# Analog_Shield.net
KiCad netlist of a schematic drawn in EAGLE
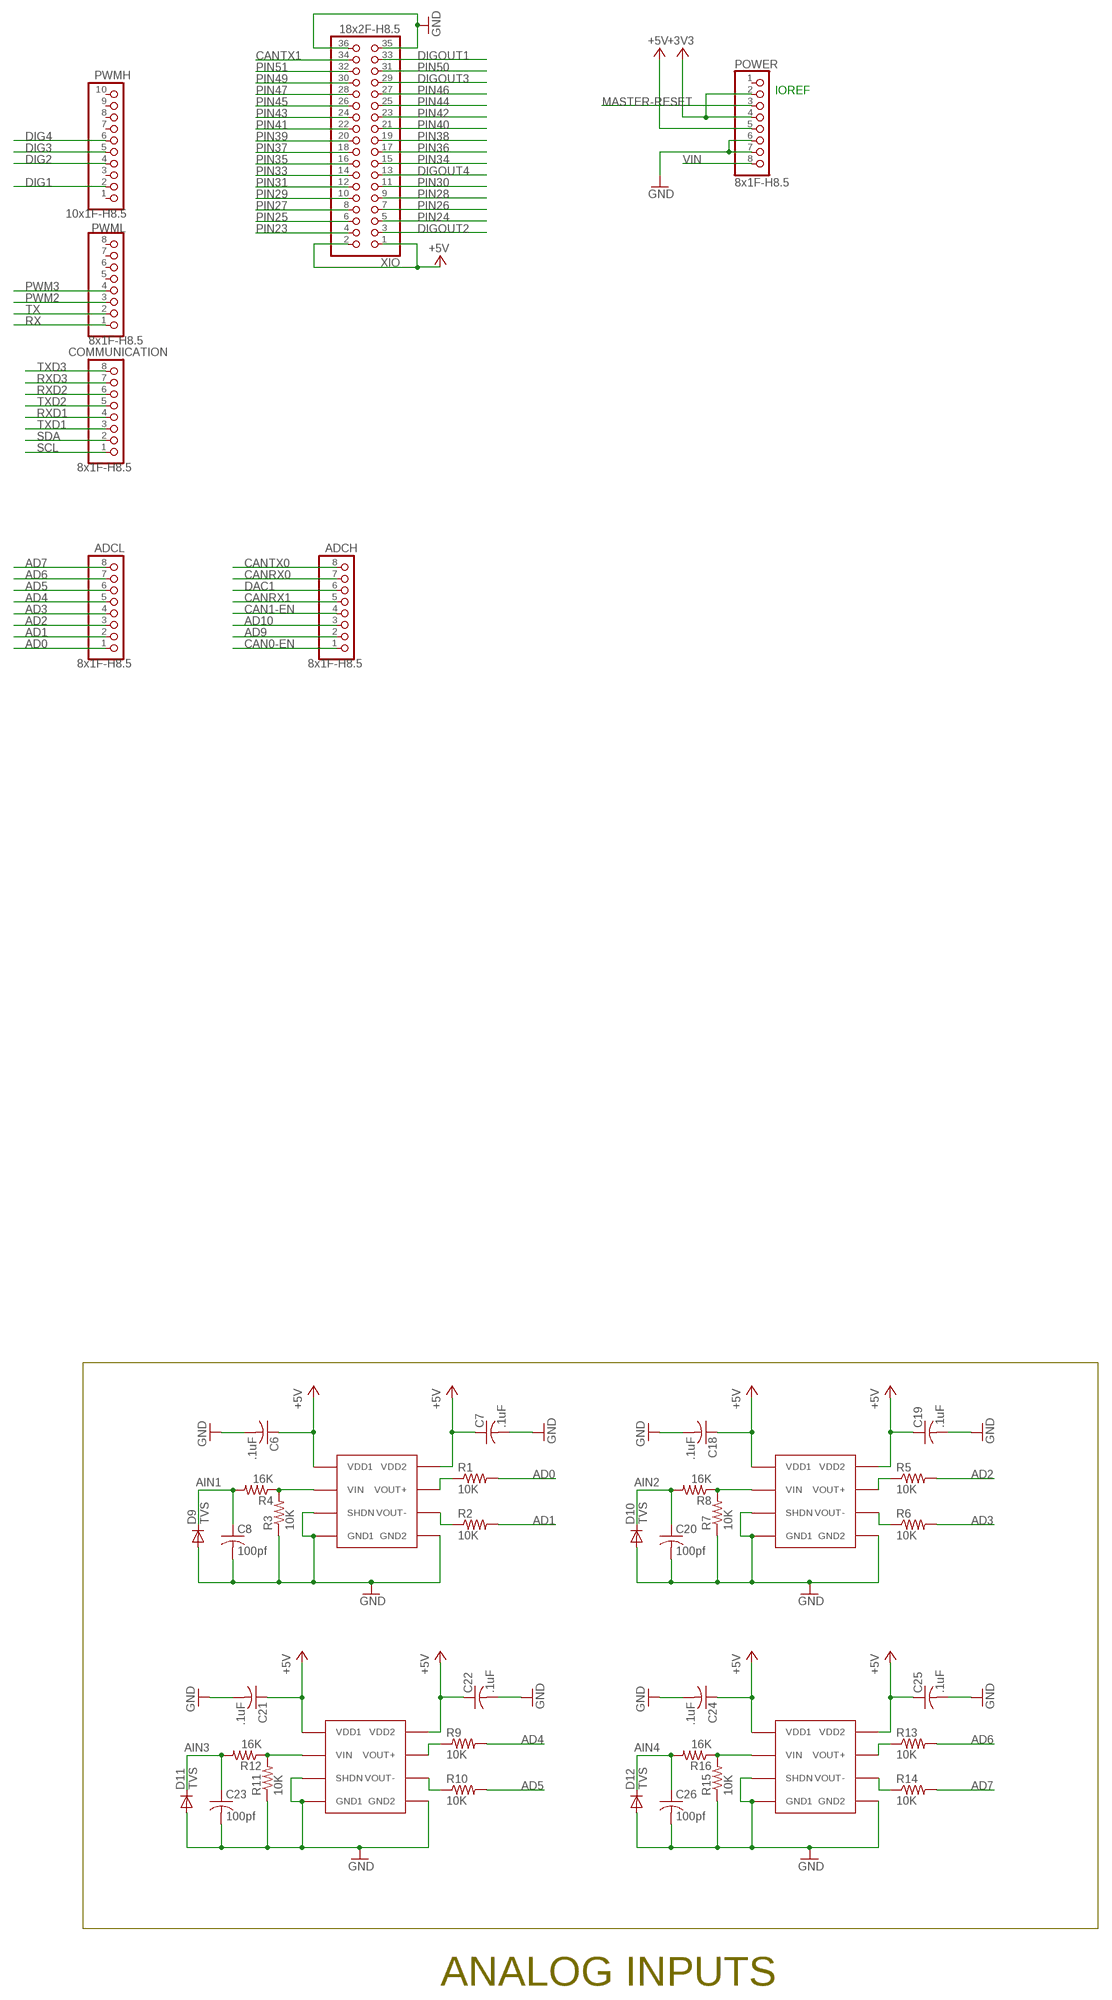
[diagram p0: schematic, sheet 1]

(export (version "E")
  (design (tool "Eeschema 10.0.6"))
  (components
    (comp (ref "ADCH")
      (value "8x1F-H8.5")
      (footprint "eagle-import:1X08")
      (libsource (lib "eagle-import") (part "PINHD-1X8"))
    )
    (comp (ref "ADCL")
      (value "8x1F-H8.5")
      (footprint "eagle-import:1X08")
      (libsource (lib "eagle-import") (part "PINHD-1X8"))
    )
    (comp (ref "C6")
      (value ".1uF")
      (footprint "eagle-import:C0603")
      (libsource (lib "eagle-import") (part "C-USC0603"))
    )
    (comp (ref "C7")
      (value ".1uF")
      (footprint "eagle-import:C0603")
      (libsource (lib "eagle-import") (part "C-USC0603"))
    )
    (comp (ref "C8")
      (value "100pf")
      (footprint "eagle-import:C0603")
      (libsource (lib "eagle-import") (part "C-USC0603"))
    )
    (comp (ref "C18")
      (value ".1uF")
      (footprint "eagle-import:C0603")
      (libsource (lib "eagle-import") (part "C-USC0603"))
    )
    (comp (ref "C19")
      (value ".1uF")
      (footprint "eagle-import:C0603")
      (libsource (lib "eagle-import") (part "C-USC0603"))
    )
    (comp (ref "C20")
      (value "100pf")
      (footprint "eagle-import:C0603")
      (libsource (lib "eagle-import") (part "C-USC0603"))
    )
    (comp (ref "C21")
      (value ".1uF")
      (footprint "eagle-import:C0603")
      (libsource (lib "eagle-import") (part "C-USC0603"))
    )
    (comp (ref "C22")
      (value ".1uF")
      (footprint "eagle-import:C0603")
      (libsource (lib "eagle-import") (part "C-USC0603"))
    )
    (comp (ref "C23")
      (value "100pf")
      (footprint "eagle-import:C0603")
      (libsource (lib "eagle-import") (part "C-USC0603"))
    )
    (comp (ref "C24")
      (value ".1uF")
      (footprint "eagle-import:C0603")
      (libsource (lib "eagle-import") (part "C-USC0603"))
    )
    (comp (ref "C25")
      (value ".1uF")
      (footprint "eagle-import:C0603")
      (libsource (lib "eagle-import") (part "C-USC0603"))
    )
    (comp (ref "C26")
      (value "100pf")
      (footprint "eagle-import:C0603")
      (libsource (lib "eagle-import") (part "C-USC0603"))
    )
    (comp (ref "COMMUNICATION")
      (value "8x1F-H8.5")
      (footprint "eagle-import:1X08")
      (libsource (lib "eagle-import") (part "PINHD-1X8"))
    )
    (comp (ref "D9")
      (value "TVS")
      (footprint "eagle-import:SOD-323")
      (libsource (lib "eagle-import") (part "DIODESOD"))
    )
    (comp (ref "D10")
      (value "TVS")
      (footprint "eagle-import:SOD-323")
      (libsource (lib "eagle-import") (part "DIODESOD"))
    )
    (comp (ref "D11")
      (value "TVS")
      (footprint "eagle-import:SOD-323")
      (libsource (lib "eagle-import") (part "DIODESOD"))
    )
    (comp (ref "D12")
      (value "TVS")
      (footprint "eagle-import:SOD-323")
      (libsource (lib "eagle-import") (part "DIODESOD"))
    )
    (comp (ref "POWER")
      (value "8x1F-H8.5")
      (footprint "eagle-import:1X08")
      (libsource (lib "eagle-import") (part "PINHD-1X8"))
    )
    (comp (ref "PWMH")
      (value "10x1F-H8.5")
      (footprint "eagle-import:1X10")
      (libsource (lib "eagle-import") (part "PINHD-1X10"))
    )
    (comp (ref "PWML")
      (value "8x1F-H8.5")
      (footprint "eagle-import:1X08")
      (libsource (lib "eagle-import") (part "PINHD-1X8"))
    )
    (comp (ref "R1")
      (value "10K")
      (footprint "eagle-import:R0603")
      (libsource (lib "eagle-import") (part "R-US_R0603"))
    )
    (comp (ref "R2")
      (value "10K")
      (footprint "eagle-import:R0603")
      (libsource (lib "eagle-import") (part "R-US_R0603"))
    )
    (comp (ref "R3")
      (value "10K")
      (footprint "eagle-import:R0603")
      (libsource (lib "eagle-import") (part "R-US_R0603"))
    )
    (comp (ref "R4")
      (value "16K")
      (footprint "eagle-import:R0603")
      (libsource (lib "eagle-import") (part "R-US_R0603"))
    )
    (comp (ref "R5")
      (value "10K")
      (footprint "eagle-import:R0603")
      (libsource (lib "eagle-import") (part "R-US_R0603"))
    )
    (comp (ref "R6")
      (value "10K")
      (footprint "eagle-import:R0603")
      (libsource (lib "eagle-import") (part "R-US_R0603"))
    )
    (comp (ref "R7")
      (value "10K")
      (footprint "eagle-import:R0603")
      (libsource (lib "eagle-import") (part "R-US_R0603"))
    )
    (comp (ref "R8")
      (value "16K")
      (footprint "eagle-import:R0603")
      (libsource (lib "eagle-import") (part "R-US_R0603"))
    )
    (comp (ref "R9")
      (value "10K")
      (footprint "eagle-import:R0603")
      (libsource (lib "eagle-import") (part "R-US_R0603"))
    )
    (comp (ref "R10")
      (value "10K")
      (footprint "eagle-import:R0603")
      (libsource (lib "eagle-import") (part "R-US_R0603"))
    )
    (comp (ref "R11")
      (value "10K")
      (footprint "eagle-import:R0603")
      (libsource (lib "eagle-import") (part "R-US_R0603"))
    )
    (comp (ref "R12")
      (value "16K")
      (footprint "eagle-import:R0603")
      (libsource (lib "eagle-import") (part "R-US_R0603"))
    )
    (comp (ref "R13")
      (value "10K")
      (footprint "eagle-import:R0603")
      (libsource (lib "eagle-import") (part "R-US_R0603"))
    )
    (comp (ref "R14")
      (value "10K")
      (footprint "eagle-import:R0603")
      (libsource (lib "eagle-import") (part "R-US_R0603"))
    )
    (comp (ref "R15")
      (value "10K")
      (footprint "eagle-import:R0603")
      (libsource (lib "eagle-import") (part "R-US_R0603"))
    )
    (comp (ref "R16")
      (value "16K")
      (footprint "eagle-import:R0603")
      (libsource (lib "eagle-import") (part "R-US_R0603"))
    )
    (comp (ref "U$1")
      (value "ACPL-C87A-000E")
      (footprint "eagle-import:SO8-WIDE")
      (libsource (lib "eagle-import") (part "ACPL-C87A-000E"))
    )
    (comp (ref "U$10")
      (value "ACPL-C87A-000E")
      (footprint "eagle-import:SO8-WIDE")
      (libsource (lib "eagle-import") (part "ACPL-C87A-000E"))
    )
    (comp (ref "U$11")
      (value "ACPL-C87A-000E")
      (footprint "eagle-import:SO8-WIDE")
      (libsource (lib "eagle-import") (part "ACPL-C87A-000E"))
    )
    (comp (ref "U$12")
      (value "ACPL-C87A-000E")
      (footprint "eagle-import:SO8-WIDE")
      (libsource (lib "eagle-import") (part "ACPL-C87A-000E"))
    )
    (comp (ref "XIO")
      (value "18x2F-H8.5")
      (footprint "eagle-import:2X18")
      (libsource (lib "eagle-import") (part "PINHD-2X18"))
    )
  )
  (nets
    (net (code "1") (name "+3V3") (class "Default")
      (node (ref "POWER") (pin "2") (pinfunction "2_2") (pintype "passive"))
      (node (ref "POWER") (pin "4") (pinfunction "4_4") (pintype "passive"))
    )
    (net (code "2") (name "+5V") (class "Default")
      (node (ref "C18") (pin "1") (pinfunction "1_1") (pintype "passive"))
      (node (ref "C19") (pin "1") (pinfunction "1_1") (pintype "passive"))
      (node (ref "C21") (pin "1") (pinfunction "1_1") (pintype "passive"))
      (node (ref "C22") (pin "1") (pinfunction "1_1") (pintype "passive"))
      (node (ref "C24") (pin "1") (pinfunction "1_1") (pintype "passive"))
      (node (ref "C25") (pin "1") (pinfunction "1_1") (pintype "passive"))
      (node (ref "C6") (pin "1") (pinfunction "1_1") (pintype "passive"))
      (node (ref "C7") (pin "1") (pinfunction "1_1") (pintype "passive"))
      (node (ref "POWER") (pin "5") (pinfunction "5_5") (pintype "passive"))
      (node (ref "U$1") (pin "1") (pinfunction "VDD1_1") (pintype "bidirectional"))
      (node (ref "U$1") (pin "8") (pinfunction "VDD2_8") (pintype "bidirectional"))
      (node (ref "U$10") (pin "1") (pinfunction "VDD1_1") (pintype "bidirectional"))
      (node (ref "U$10") (pin "8") (pinfunction "VDD2_8") (pintype "bidirectional"))
      (node (ref "U$11") (pin "1") (pinfunction "VDD1_1") (pintype "bidirectional"))
      (node (ref "U$11") (pin "8") (pinfunction "VDD2_8") (pintype "bidirectional"))
      (node (ref "U$12") (pin "1") (pinfunction "VDD1_1") (pintype "bidirectional"))
      (node (ref "U$12") (pin "8") (pinfunction "VDD2_8") (pintype "bidirectional"))
      (node (ref "XIO") (pin "1") (pinfunction "1_1") (pintype "passive"))
      (node (ref "XIO") (pin "2") (pinfunction "2_2") (pintype "passive"))
    )
    (net (code "3") (name "/AD0") (class "Default")
      (node (ref "ADCL") (pin "1") (pinfunction "1_1") (pintype "passive"))
      (node (ref "R1") (pin "2") (pinfunction "2_2") (pintype "passive"))
    )
    (net (code "4") (name "/AD1") (class "Default")
      (node (ref "ADCL") (pin "2") (pinfunction "2_2") (pintype "passive"))
      (node (ref "R2") (pin "2") (pinfunction "2_2") (pintype "passive"))
    )
    (net (code "5") (name "/AD2") (class "Default")
      (node (ref "ADCL") (pin "3") (pinfunction "3_3") (pintype "passive"))
      (node (ref "R5") (pin "2") (pinfunction "2_2") (pintype "passive"))
    )
    (net (code "6") (name "/AD3") (class "Default")
      (node (ref "ADCL") (pin "4") (pinfunction "4_4") (pintype "passive"))
      (node (ref "R6") (pin "2") (pinfunction "2_2") (pintype "passive"))
    )
    (net (code "7") (name "/AD4") (class "Default")
      (node (ref "ADCL") (pin "5") (pinfunction "5_5") (pintype "passive"))
      (node (ref "R9") (pin "2") (pinfunction "2_2") (pintype "passive"))
    )
    (net (code "8") (name "/AD5") (class "Default")
      (node (ref "ADCL") (pin "6") (pinfunction "6_6") (pintype "passive"))
      (node (ref "R10") (pin "2") (pinfunction "2_2") (pintype "passive"))
    )
    (net (code "9") (name "/AD6") (class "Default")
      (node (ref "ADCL") (pin "7") (pinfunction "7_7") (pintype "passive"))
      (node (ref "R13") (pin "2") (pinfunction "2_2") (pintype "passive"))
    )
    (net (code "10") (name "/AD7") (class "Default")
      (node (ref "ADCL") (pin "8") (pinfunction "8_8") (pintype "passive"))
      (node (ref "R14") (pin "2") (pinfunction "2_2") (pintype "passive"))
    )
    (net (code "11") (name "/AD9") (class "Default")
      (node (ref "ADCH") (pin "2") (pinfunction "2_2") (pintype "passive"))
    )
    (net (code "12") (name "/AD10") (class "Default")
      (node (ref "ADCH") (pin "3") (pinfunction "3_3") (pintype "passive"))
    )
    (net (code "13") (name "/AIN1") (class "Default")
      (node (ref "C8") (pin "1") (pinfunction "1_1") (pintype "passive"))
      (node (ref "D9") (pin "1") (pinfunction "C_1") (pintype "passive"))
      (node (ref "R4") (pin "2") (pinfunction "2_2") (pintype "passive"))
    )
    (net (code "14") (name "/AIN2") (class "Default")
      (node (ref "C20") (pin "1") (pinfunction "1_1") (pintype "passive"))
      (node (ref "D10") (pin "1") (pinfunction "C_1") (pintype "passive"))
      (node (ref "R8") (pin "2") (pinfunction "2_2") (pintype "passive"))
    )
    (net (code "15") (name "/AIN3") (class "Default")
      (node (ref "C23") (pin "1") (pinfunction "1_1") (pintype "passive"))
      (node (ref "D11") (pin "1") (pinfunction "C_1") (pintype "passive"))
      (node (ref "R12") (pin "2") (pinfunction "2_2") (pintype "passive"))
    )
    (net (code "16") (name "/AIN4") (class "Default")
      (node (ref "C26") (pin "1") (pinfunction "1_1") (pintype "passive"))
      (node (ref "D12") (pin "1") (pinfunction "C_1") (pintype "passive"))
      (node (ref "R16") (pin "2") (pinfunction "2_2") (pintype "passive"))
    )
    (net (code "17") (name "/CAN0-EN") (class "Default")
      (node (ref "ADCH") (pin "1") (pinfunction "1_1") (pintype "passive"))
    )
    (net (code "18") (name "/CAN1-EN") (class "Default")
      (node (ref "ADCH") (pin "4") (pinfunction "4_4") (pintype "passive"))
    )
    (net (code "19") (name "/CANRX0") (class "Default")
      (node (ref "ADCH") (pin "7") (pinfunction "7_7") (pintype "passive"))
    )
    (net (code "20") (name "/CANRX1") (class "Default")
      (node (ref "ADCH") (pin "5") (pinfunction "5_5") (pintype "passive"))
    )
    (net (code "21") (name "/CANTX0") (class "Default")
      (node (ref "ADCH") (pin "8") (pinfunction "8_8") (pintype "passive"))
    )
    (net (code "22") (name "/CANTX1") (class "Default")
      (node (ref "XIO") (pin "34") (pinfunction "34_34") (pintype "passive"))
    )
    (net (code "23") (name "/DAC1") (class "Default")
      (node (ref "ADCH") (pin "6") (pinfunction "6_6") (pintype "passive"))
    )
    (net (code "24") (name "/DIG1") (class "Default")
      (node (ref "PWMH") (pin "2") (pinfunction "2_2") (pintype "passive"))
    )
    (net (code "25") (name "/DIG2") (class "Default")
      (node (ref "PWMH") (pin "4") (pinfunction "4_4") (pintype "passive"))
    )
    (net (code "26") (name "/DIG3") (class "Default")
      (node (ref "PWMH") (pin "5") (pinfunction "5_5") (pintype "passive"))
    )
    (net (code "27") (name "/DIG4") (class "Default")
      (node (ref "PWMH") (pin "6") (pinfunction "6_6") (pintype "passive"))
    )
    (net (code "28") (name "/DIGOUT1") (class "Default")
      (node (ref "XIO") (pin "33") (pinfunction "33_33") (pintype "passive"))
    )
    (net (code "29") (name "/DIGOUT2") (class "Default")
      (node (ref "XIO") (pin "3") (pinfunction "3_3") (pintype "passive"))
    )
    (net (code "30") (name "/DIGOUT3") (class "Default")
      (node (ref "XIO") (pin "29") (pinfunction "29_29") (pintype "passive"))
    )
    (net (code "31") (name "/DIGOUT4") (class "Default")
      (node (ref "XIO") (pin "13") (pinfunction "13_13") (pintype "passive"))
    )
    (net (code "32") (name "/MASTER-RESET") (class "Default")
      (node (ref "POWER") (pin "3") (pinfunction "3_3") (pintype "passive"))
    )
    (net (code "33") (name "/PIN23") (class "Default")
      (node (ref "XIO") (pin "4") (pinfunction "4_4") (pintype "passive"))
    )
    (net (code "34") (name "/PIN24") (class "Default")
      (node (ref "XIO") (pin "5") (pinfunction "5_5") (pintype "passive"))
    )
    (net (code "35") (name "/PIN25") (class "Default")
      (node (ref "XIO") (pin "6") (pinfunction "6_6") (pintype "passive"))
    )
    (net (code "36") (name "/PIN26") (class "Default")
      (node (ref "XIO") (pin "7") (pinfunction "7_7") (pintype "passive"))
    )
    (net (code "37") (name "/PIN27") (class "Default")
      (node (ref "XIO") (pin "8") (pinfunction "8_8") (pintype "passive"))
    )
    (net (code "38") (name "/PIN28") (class "Default")
      (node (ref "XIO") (pin "9") (pinfunction "9_9") (pintype "passive"))
    )
    (net (code "39") (name "/PIN29") (class "Default")
      (node (ref "XIO") (pin "10") (pinfunction "10_10") (pintype "passive"))
    )
    (net (code "40") (name "/PIN30") (class "Default")
      (node (ref "XIO") (pin "11") (pinfunction "11_11") (pintype "passive"))
    )
    (net (code "41") (name "/PIN31") (class "Default")
      (node (ref "XIO") (pin "12") (pinfunction "12_12") (pintype "passive"))
    )
    (net (code "42") (name "/PIN33") (class "Default")
      (node (ref "XIO") (pin "14") (pinfunction "14_14") (pintype "passive"))
    )
    (net (code "43") (name "/PIN34") (class "Default")
      (node (ref "XIO") (pin "15") (pinfunction "15_15") (pintype "passive"))
    )
    (net (code "44") (name "/PIN35") (class "Default")
      (node (ref "XIO") (pin "16") (pinfunction "16_16") (pintype "passive"))
    )
    (net (code "45") (name "/PIN36") (class "Default")
      (node (ref "XIO") (pin "17") (pinfunction "17_17") (pintype "passive"))
    )
    (net (code "46") (name "/PIN37") (class "Default")
      (node (ref "XIO") (pin "18") (pinfunction "18_18") (pintype "passive"))
    )
    (net (code "47") (name "/PIN38") (class "Default")
      (node (ref "XIO") (pin "19") (pinfunction "19_19") (pintype "passive"))
    )
    (net (code "48") (name "/PIN39") (class "Default")
      (node (ref "XIO") (pin "20") (pinfunction "20_20") (pintype "passive"))
    )
    (net (code "49") (name "/PIN40") (class "Default")
      (node (ref "XIO") (pin "21") (pinfunction "21_21") (pintype "passive"))
    )
    (net (code "50") (name "/PIN41") (class "Default")
      (node (ref "XIO") (pin "22") (pinfunction "22_22") (pintype "passive"))
    )
    (net (code "51") (name "/PIN42") (class "Default")
      (node (ref "XIO") (pin "23") (pinfunction "23_23") (pintype "passive"))
    )
    (net (code "52") (name "/PIN43") (class "Default")
      (node (ref "XIO") (pin "24") (pinfunction "24_24") (pintype "passive"))
    )
    (net (code "53") (name "/PIN44") (class "Default")
      (node (ref "XIO") (pin "25") (pinfunction "25_25") (pintype "passive"))
    )
    (net (code "54") (name "/PIN45") (class "Default")
      (node (ref "XIO") (pin "26") (pinfunction "26_26") (pintype "passive"))
    )
    (net (code "55") (name "/PIN46") (class "Default")
      (node (ref "XIO") (pin "27") (pinfunction "27_27") (pintype "passive"))
    )
    (net (code "56") (name "/PIN47") (class "Default")
      (node (ref "XIO") (pin "28") (pinfunction "28_28") (pintype "passive"))
    )
    (net (code "57") (name "/PIN49") (class "Default")
      (node (ref "XIO") (pin "30") (pinfunction "30_30") (pintype "passive"))
    )
    (net (code "58") (name "/PIN50") (class "Default")
      (node (ref "XIO") (pin "31") (pinfunction "31_31") (pintype "passive"))
    )
    (net (code "59") (name "/PIN51") (class "Default")
      (node (ref "XIO") (pin "32") (pinfunction "32_32") (pintype "passive"))
    )
    (net (code "60") (name "/PWM2") (class "Default")
      (node (ref "PWML") (pin "3") (pinfunction "3_3") (pintype "passive"))
    )
    (net (code "61") (name "/PWM3") (class "Default")
      (node (ref "PWML") (pin "4") (pinfunction "4_4") (pintype "passive"))
    )
    (net (code "62") (name "/RX") (class "Default")
      (node (ref "PWML") (pin "1") (pinfunction "1_1") (pintype "passive"))
    )
    (net (code "63") (name "/RXD1") (class "Default")
      (node (ref "COMMUNICATION") (pin "4") (pinfunction "4_4") (pintype "passive"))
    )
    (net (code "64") (name "/RXD2") (class "Default")
      (node (ref "COMMUNICATION") (pin "6") (pinfunction "6_6") (pintype "passive"))
    )
    (net (code "65") (name "/RXD3") (class "Default")
      (node (ref "COMMUNICATION") (pin "7") (pinfunction "7_7") (pintype "passive"))
    )
    (net (code "66") (name "/SCL") (class "Default")
      (node (ref "COMMUNICATION") (pin "1") (pinfunction "1_1") (pintype "passive"))
    )
    (net (code "67") (name "/SDA") (class "Default")
      (node (ref "COMMUNICATION") (pin "2") (pinfunction "2_2") (pintype "passive"))
    )
    (net (code "68") (name "/TX") (class "Default")
      (node (ref "PWML") (pin "2") (pinfunction "2_2") (pintype "passive"))
    )
    (net (code "69") (name "/TXD1") (class "Default")
      (node (ref "COMMUNICATION") (pin "3") (pinfunction "3_3") (pintype "passive"))
    )
    (net (code "70") (name "/TXD2") (class "Default")
      (node (ref "COMMUNICATION") (pin "5") (pinfunction "5_5") (pintype "passive"))
    )
    (net (code "71") (name "/TXD3") (class "Default")
      (node (ref "COMMUNICATION") (pin "8") (pinfunction "8_8") (pintype "passive"))
    )
    (net (code "72") (name "/VIN") (class "Default")
      (node (ref "POWER") (pin "8") (pinfunction "8_8") (pintype "passive"))
    )
    (net (code "73") (name "GND") (class "Default")
      (node (ref "C18") (pin "2") (pinfunction "2_2") (pintype "passive"))
      (node (ref "C19") (pin "2") (pinfunction "2_2") (pintype "passive"))
      (node (ref "C20") (pin "2") (pinfunction "2_2") (pintype "passive"))
      (node (ref "C21") (pin "2") (pinfunction "2_2") (pintype "passive"))
      (node (ref "C22") (pin "2") (pinfunction "2_2") (pintype "passive"))
      (node (ref "C23") (pin "2") (pinfunction "2_2") (pintype "passive"))
      (node (ref "C24") (pin "2") (pinfunction "2_2") (pintype "passive"))
      (node (ref "C25") (pin "2") (pinfunction "2_2") (pintype "passive"))
      (node (ref "C26") (pin "2") (pinfunction "2_2") (pintype "passive"))
      (node (ref "C6") (pin "2") (pinfunction "2_2") (pintype "passive"))
      (node (ref "C7") (pin "2") (pinfunction "2_2") (pintype "passive"))
      (node (ref "C8") (pin "2") (pinfunction "2_2") (pintype "passive"))
      (node (ref "D10") (pin "2") (pinfunction "A_2") (pintype "passive"))
      (node (ref "D11") (pin "2") (pinfunction "A_2") (pintype "passive"))
      (node (ref "D12") (pin "2") (pinfunction "A_2") (pintype "passive"))
      (node (ref "D9") (pin "2") (pinfunction "A_2") (pintype "passive"))
      (node (ref "POWER") (pin "6") (pinfunction "6_6") (pintype "passive"))
      (node (ref "POWER") (pin "7") (pinfunction "7_7") (pintype "passive"))
      (node (ref "R11") (pin "1") (pinfunction "1_1") (pintype "passive"))
      (node (ref "R15") (pin "1") (pinfunction "1_1") (pintype "passive"))
      (node (ref "R3") (pin "1") (pinfunction "1_1") (pintype "passive"))
      (node (ref "R7") (pin "1") (pinfunction "1_1") (pintype "passive"))
      (node (ref "U$1") (pin "3") (pinfunction "SHDN_3") (pintype "bidirectional"))
      (node (ref "U$1") (pin "4") (pinfunction "GND1_4") (pintype "bidirectional"))
      (node (ref "U$1") (pin "5") (pinfunction "GND2_5") (pintype "bidirectional"))
      (node (ref "U$10") (pin "3") (pinfunction "SHDN_3") (pintype "bidirectional"))
      (node (ref "U$10") (pin "4") (pinfunction "GND1_4") (pintype "bidirectional"))
      (node (ref "U$10") (pin "5") (pinfunction "GND2_5") (pintype "bidirectional"))
      (node (ref "U$11") (pin "3") (pinfunction "SHDN_3") (pintype "bidirectional"))
      (node (ref "U$11") (pin "4") (pinfunction "GND1_4") (pintype "bidirectional"))
      (node (ref "U$11") (pin "5") (pinfunction "GND2_5") (pintype "bidirectional"))
      (node (ref "U$12") (pin "3") (pinfunction "SHDN_3") (pintype "bidirectional"))
      (node (ref "U$12") (pin "4") (pinfunction "GND1_4") (pintype "bidirectional"))
      (node (ref "U$12") (pin "5") (pinfunction "GND2_5") (pintype "bidirectional"))
      (node (ref "XIO") (pin "35") (pinfunction "35_35") (pintype "passive"))
      (node (ref "XIO") (pin "36") (pinfunction "36_36") (pintype "passive"))
    )
    (net (code "74") (name "Net-(U$1-VIN)") (class "Default")
      (node (ref "R3") (pin "2") (pinfunction "2_2") (pintype "passive"))
      (node (ref "R4") (pin "1") (pinfunction "1_1") (pintype "passive"))
      (node (ref "U$1") (pin "2") (pinfunction "VIN_2") (pintype "bidirectional"))
    )
    (net (code "75") (name "Net-(U$1-VOUT+)") (class "Default")
      (node (ref "R1") (pin "1") (pinfunction "1_1") (pintype "passive"))
      (node (ref "U$1") (pin "7") (pinfunction "VOUT+_7") (pintype "bidirectional"))
    )
    (net (code "76") (name "Net-(U$1-VOUT-)") (class "Default")
      (node (ref "R2") (pin "1") (pinfunction "1_1") (pintype "passive"))
      (node (ref "U$1") (pin "6") (pinfunction "VOUT-_6") (pintype "bidirectional"))
    )
    (net (code "77") (name "Net-(U$10-VIN)") (class "Default")
      (node (ref "R7") (pin "2") (pinfunction "2_2") (pintype "passive"))
      (node (ref "R8") (pin "1") (pinfunction "1_1") (pintype "passive"))
      (node (ref "U$10") (pin "2") (pinfunction "VIN_2") (pintype "bidirectional"))
    )
    (net (code "78") (name "Net-(U$10-VOUT+)") (class "Default")
      (node (ref "R5") (pin "1") (pinfunction "1_1") (pintype "passive"))
      (node (ref "U$10") (pin "7") (pinfunction "VOUT+_7") (pintype "bidirectional"))
    )
    (net (code "79") (name "Net-(U$10-VOUT-)") (class "Default")
      (node (ref "R6") (pin "1") (pinfunction "1_1") (pintype "passive"))
      (node (ref "U$10") (pin "6") (pinfunction "VOUT-_6") (pintype "bidirectional"))
    )
    (net (code "80") (name "Net-(U$11-VIN)") (class "Default")
      (node (ref "R11") (pin "2") (pinfunction "2_2") (pintype "passive"))
      (node (ref "R12") (pin "1") (pinfunction "1_1") (pintype "passive"))
      (node (ref "U$11") (pin "2") (pinfunction "VIN_2") (pintype "bidirectional"))
    )
    (net (code "81") (name "Net-(U$11-VOUT+)") (class "Default")
      (node (ref "R9") (pin "1") (pinfunction "1_1") (pintype "passive"))
      (node (ref "U$11") (pin "7") (pinfunction "VOUT+_7") (pintype "bidirectional"))
    )
    (net (code "82") (name "Net-(U$11-VOUT-)") (class "Default")
      (node (ref "R10") (pin "1") (pinfunction "1_1") (pintype "passive"))
      (node (ref "U$11") (pin "6") (pinfunction "VOUT-_6") (pintype "bidirectional"))
    )
    (net (code "83") (name "Net-(U$12-VIN)") (class "Default")
      (node (ref "R15") (pin "2") (pinfunction "2_2") (pintype "passive"))
      (node (ref "R16") (pin "1") (pinfunction "1_1") (pintype "passive"))
      (node (ref "U$12") (pin "2") (pinfunction "VIN_2") (pintype "bidirectional"))
    )
    (net (code "84") (name "Net-(U$12-VOUT+)") (class "Default")
      (node (ref "R13") (pin "1") (pinfunction "1_1") (pintype "passive"))
      (node (ref "U$12") (pin "7") (pinfunction "VOUT+_7") (pintype "bidirectional"))
    )
    (net (code "85") (name "Net-(U$12-VOUT-)") (class "Default")
      (node (ref "R14") (pin "1") (pinfunction "1_1") (pintype "passive"))
      (node (ref "U$12") (pin "6") (pinfunction "VOUT-_6") (pintype "bidirectional"))
    )
    (net (code "86") (name "unconnected-(POWER-Pad1)") (class "Default")
      (node (ref "POWER") (pin "1") (pinfunction "1_1") (pintype "passive"))
    )
    (net (code "87") (name "unconnected-(PWMH-Pad1)") (class "Default")
      (node (ref "PWMH") (pin "1") (pinfunction "1_1") (pintype "passive"))
    )
    (net (code "88") (name "unconnected-(PWMH-Pad3)") (class "Default")
      (node (ref "PWMH") (pin "3") (pinfunction "3_3") (pintype "passive"))
    )
    (net (code "89") (name "unconnected-(PWMH-Pad7)") (class "Default")
      (node (ref "PWMH") (pin "7") (pinfunction "7_7") (pintype "passive"))
    )
    (net (code "90") (name "unconnected-(PWMH-Pad8)") (class "Default")
      (node (ref "PWMH") (pin "8") (pinfunction "8_8") (pintype "passive"))
    )
    (net (code "91") (name "unconnected-(PWMH-Pad9)") (class "Default")
      (node (ref "PWMH") (pin "9") (pinfunction "9_9") (pintype "passive"))
    )
    (net (code "92") (name "unconnected-(PWMH-Pad10)") (class "Default")
      (node (ref "PWMH") (pin "10") (pinfunction "10_10") (pintype "passive"))
    )
    (net (code "93") (name "unconnected-(PWML-Pad5)") (class "Default")
      (node (ref "PWML") (pin "5") (pinfunction "5_5") (pintype "passive"))
    )
    (net (code "94") (name "unconnected-(PWML-Pad6)") (class "Default")
      (node (ref "PWML") (pin "6") (pinfunction "6_6") (pintype "passive"))
    )
    (net (code "95") (name "unconnected-(PWML-Pad7)") (class "Default")
      (node (ref "PWML") (pin "7") (pinfunction "7_7") (pintype "passive"))
    )
    (net (code "96") (name "unconnected-(PWML-Pad8)") (class "Default")
      (node (ref "PWML") (pin "8") (pinfunction "8_8") (pintype "passive"))
    )
  )
)
